# transimpedance_amplifier_soic8.net
KiCad netlist of a schematic drawn in EAGLE
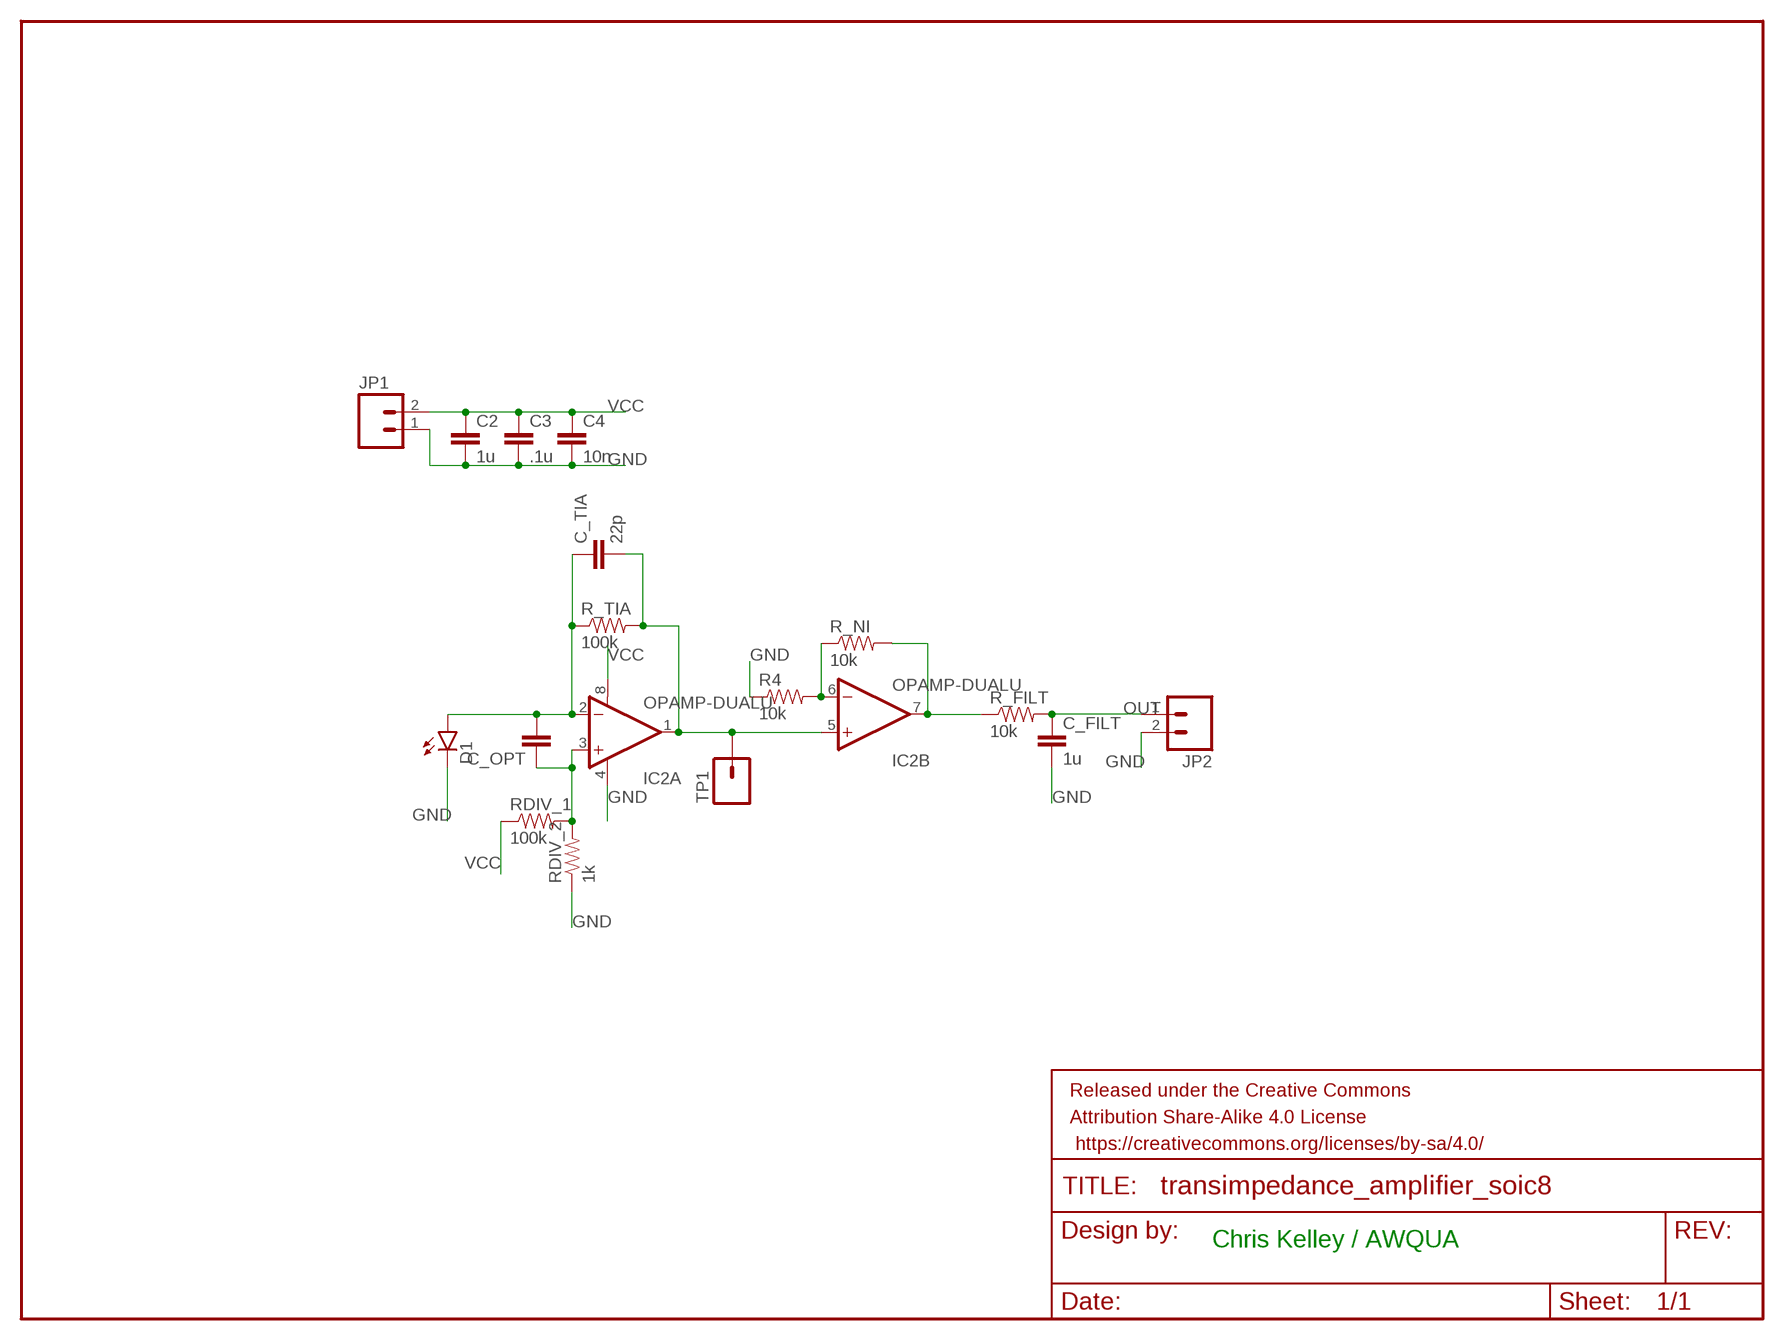
[diagram p0: schematic, sheet 1]

(export (version "E")
  (design (tool "Eeschema 10.0.6"))
  (components
    (comp (ref "C2")
      (value "1u")
      (footprint "eagle-import:0805")
      (libsource (lib "eagle-import") (part "CAP0805"))
    )
    (comp (ref "C3")
      (value ".1u")
      (footprint "eagle-import:0805")
      (libsource (lib "eagle-import") (part "CAP0805"))
    )
    (comp (ref "C4")
      (value "10n")
      (footprint "eagle-import:0805")
      (libsource (lib "eagle-import") (part "CAP0805"))
    )
    (comp (ref "C_FILT")
      (value "1u")
      (footprint "eagle-import:0805")
      (libsource (lib "eagle-import") (part "CAP0805"))
    )
    (comp (ref "C_OPT")
      (value "CAP0805")
      (footprint "eagle-import:0805")
      (libsource (lib "eagle-import") (part "CAP0805"))
    )
    (comp (ref "C_TIA")
      (value "22p")
      (footprint "eagle-import:0805")
      (libsource (lib "eagle-import") (part "CAP0805"))
    )
    (comp (ref "D1")
      (value "LED5MM")
      (footprint "eagle-import:LED5MM")
      (libsource (lib "eagle-import") (part "LED5MM"))
    )
    (comp (ref "FRAME1")
      (value "FRAME-LETTER")
      (footprint "eagle-import:CREATIVE_COMMONS")
      (libsource (lib "eagle-import") (part "FRAME-LETTER"))
    )
    (comp (ref "IC2")
      (value "OPAMP-DUALU")
      (footprint "eagle-import:SO08")
      (libsource (lib "eagle-import") (part "OPAMP-DUALU"))
    )
    (comp (ref "JP1")
      (value "M02PTH")
      (footprint "eagle-import:1X02")
      (libsource (lib "eagle-import") (part "M02PTH"))
    )
    (comp (ref "JP2")
      (value "M02PTH")
      (footprint "eagle-import:1X02")
      (libsource (lib "eagle-import") (part "M02PTH"))
    )
    (comp (ref "R4")
      (value "10k")
      (footprint "eagle-import:0603-RES")
      (libsource (lib "eagle-import") (part "RESISTOR0603-RES"))
    )
    (comp (ref "RDIV_1")
      (value "100k")
      (footprint "eagle-import:0603-RES")
      (libsource (lib "eagle-import") (part "RESISTOR0603-RES"))
    )
    (comp (ref "RDIV_2")
      (value "1k")
      (footprint "eagle-import:0603-RES")
      (libsource (lib "eagle-import") (part "RESISTOR0603-RES"))
    )
    (comp (ref "R_FILT")
      (value "10k")
      (footprint "eagle-import:0603-RES")
      (libsource (lib "eagle-import") (part "RESISTOR0603-RES"))
    )
    (comp (ref "R_NI")
      (value "10k")
      (footprint "eagle-import:0603-RES")
      (libsource (lib "eagle-import") (part "RESISTOR0603-RES"))
    )
    (comp (ref "R_TIA")
      (value "100k")
      (footprint "eagle-import:0603-RES")
      (libsource (lib "eagle-import") (part "RESISTOR0603-RES"))
    )
    (comp (ref "TP1")
      (value "M01PTH")
      (footprint "eagle-import:1X01")
      (libsource (lib "eagle-import") (part "M01PTH"))
    )
  )
  (nets
    (net (code "1") (name "/GND") (class "Default")
      (node (ref "C2") (pin "2") (pinfunction "2_2") (pintype "passive"))
      (node (ref "C3") (pin "2") (pinfunction "2_2") (pintype "passive"))
      (node (ref "C4") (pin "2") (pinfunction "2_2") (pintype "passive"))
      (node (ref "C_FILT") (pin "2") (pinfunction "2_2") (pintype "passive"))
      (node (ref "D1") (pin "K") (pinfunction "C_K") (pintype "passive"))
      (node (ref "IC2") (pin "4") (pinfunction "V-_4") (pintype "power_in"))
      (node (ref "JP1") (pin "1") (pinfunction "1_1") (pintype "passive"))
      (node (ref "JP2") (pin "2") (pinfunction "2_2") (pintype "passive"))
      (node (ref "R4") (pin "1") (pinfunction "1_1") (pintype "passive"))
      (node (ref "RDIV_2") (pin "1") (pinfunction "1_1") (pintype "passive"))
    )
    (net (code "2") (name "/OUT") (class "Default")
      (node (ref "C_FILT") (pin "1") (pinfunction "1_1") (pintype "passive"))
      (node (ref "JP2") (pin "1") (pinfunction "1_1") (pintype "passive"))
      (node (ref "R_FILT") (pin "2") (pinfunction "2_2") (pintype "passive"))
    )
    (net (code "3") (name "/VCC") (class "Default")
      (node (ref "C2") (pin "1") (pinfunction "1_1") (pintype "passive"))
      (node (ref "C3") (pin "1") (pinfunction "1_1") (pintype "passive"))
      (node (ref "C4") (pin "1") (pinfunction "1_1") (pintype "passive"))
      (node (ref "IC2") (pin "8") (pinfunction "V+_8") (pintype "power_in"))
      (node (ref "JP1") (pin "2") (pinfunction "2_2") (pintype "passive"))
      (node (ref "RDIV_1") (pin "1") (pinfunction "1_1") (pintype "passive"))
    )
    (net (code "4") (name "Net-(IC2A-+IN)") (class "Default")
      (node (ref "C_OPT") (pin "1") (pinfunction "1_1") (pintype "passive"))
      (node (ref "IC2") (pin "3") (pinfunction "+IN_3") (pintype "input"))
      (node (ref "RDIV_1") (pin "2") (pinfunction "2_2") (pintype "passive"))
      (node (ref "RDIV_2") (pin "2") (pinfunction "2_2") (pintype "passive"))
    )
    (net (code "5") (name "Net-(IC2A--IN)") (class "Default")
      (node (ref "C_OPT") (pin "2") (pinfunction "2_2") (pintype "passive"))
      (node (ref "C_TIA") (pin "1") (pinfunction "1_1") (pintype "passive"))
      (node (ref "D1") (pin "A") (pinfunction "A_A") (pintype "passive"))
      (node (ref "IC2") (pin "2") (pinfunction "-IN_2") (pintype "input"))
      (node (ref "R_TIA") (pin "1") (pinfunction "1_1") (pintype "passive"))
    )
    (net (code "6") (name "Net-(IC2A-OUT)") (class "Default")
      (node (ref "C_TIA") (pin "2") (pinfunction "2_2") (pintype "passive"))
      (node (ref "IC2") (pin "1") (pinfunction "OUT_1") (pintype "output"))
      (node (ref "IC2") (pin "5") (pinfunction "+IN_5") (pintype "input"))
      (node (ref "R_TIA") (pin "2") (pinfunction "2_2") (pintype "passive"))
      (node (ref "TP1") (pin "1") (pinfunction "1_1") (pintype "passive"))
    )
    (net (code "7") (name "Net-(IC2B--IN)") (class "Default")
      (node (ref "IC2") (pin "6") (pinfunction "-IN_6") (pintype "input"))
      (node (ref "R4") (pin "2") (pinfunction "2_2") (pintype "passive"))
      (node (ref "R_NI") (pin "1") (pinfunction "1_1") (pintype "passive"))
    )
    (net (code "8") (name "Net-(IC2B-OUT)") (class "Default")
      (node (ref "IC2") (pin "7") (pinfunction "OUT_7") (pintype "output"))
      (node (ref "R_FILT") (pin "1") (pinfunction "1_1") (pintype "passive"))
      (node (ref "R_NI") (pin "2") (pinfunction "2_2") (pintype "passive"))
    )
  )
)
